# LEDs.net
KiCad netlist of a schematic drawn in Altium Designer
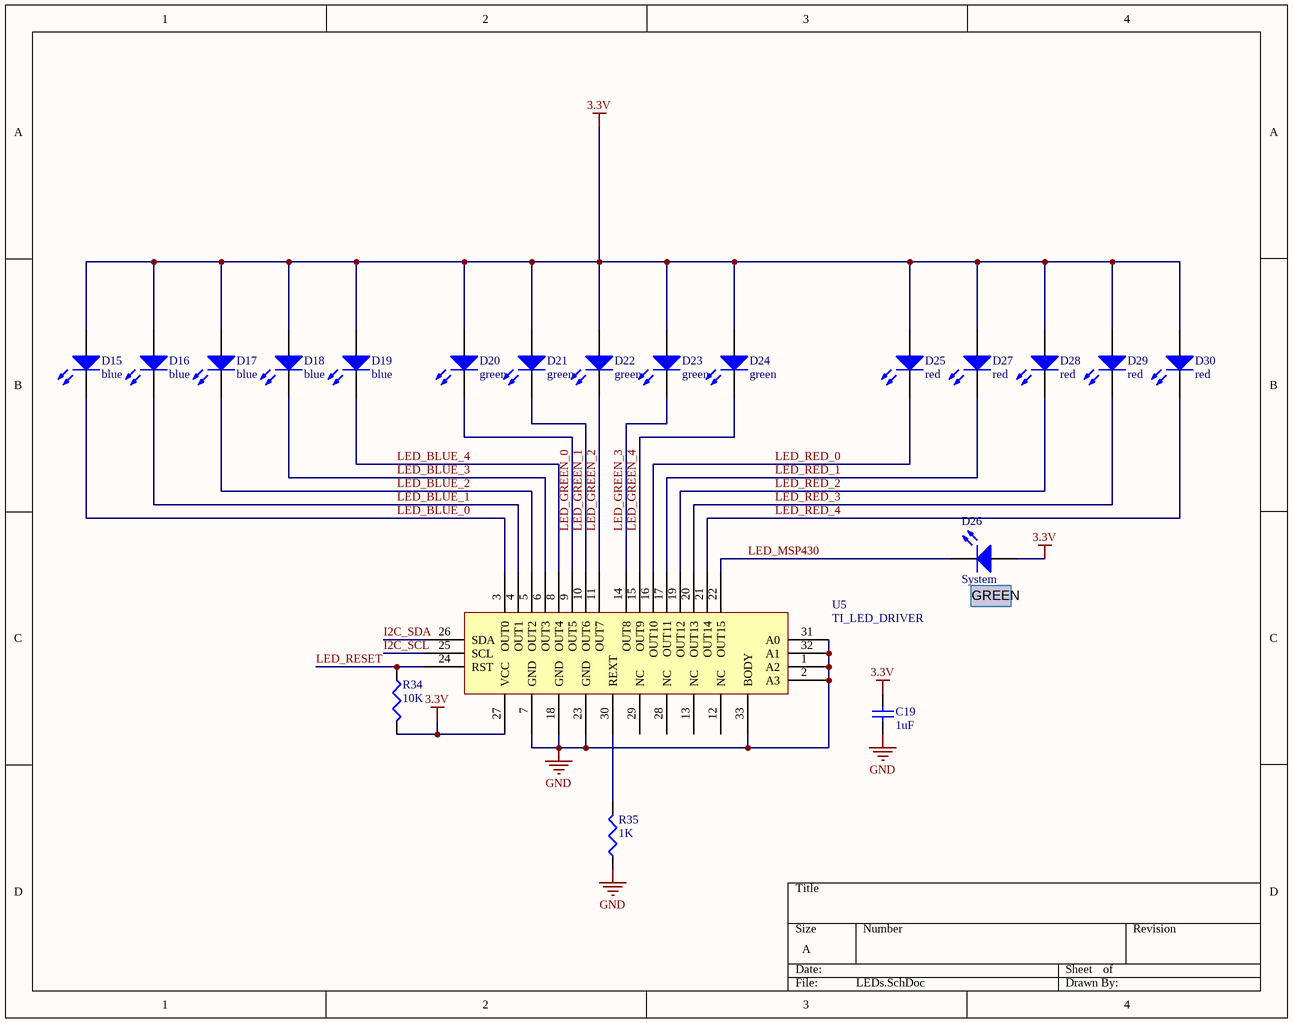
[diagram p0: LEDs.SchDoc]

(export (version "E")
  (design (tool "Eeschema 10.0.6"))
  (components
    (comp (ref "C19")
      (value "1uF")
      (footprint "CAPC1608L")
      (description "Capacitor (Semiconductor SIM Model)")
      (fields (field (name "Comment") "Cap Semi") (field (name "PUBLISHER") "Altium Limited"))
      (libsource (lib "Miscellaneous Devices") (part "Cap Semi"))
    )
    (comp (ref "D15") (value "blue") (footprint "SurfaceMount(603)") (libsource (lib "") (part "LED_1")))
    (comp (ref "D16") (value "blue") (footprint "SurfaceMount(603)") (libsource (lib "") (part "LED_1")))
    (comp (ref "D17") (value "blue") (footprint "SurfaceMount(603)") (libsource (lib "") (part "LED_1")))
    (comp (ref "D18") (value "blue") (footprint "SurfaceMount(603)") (libsource (lib "") (part "LED_1")))
    (comp (ref "D19") (value "blue") (footprint "SurfaceMount(603)") (libsource (lib "") (part "LED_1")))
    (comp (ref "D20") (value "green") (footprint "SurfaceMount(603)") (libsource (lib "") (part "LED_1")))
    (comp (ref "D21") (value "green") (footprint "SurfaceMount(603)") (libsource (lib "") (part "LED_1")))
    (comp (ref "D22") (value "green") (footprint "SurfaceMount(603)") (libsource (lib "") (part "LED_1")))
    (comp (ref "D23") (value "green") (footprint "SurfaceMount(603)") (libsource (lib "") (part "LED_1")))
    (comp (ref "D24") (value "green") (footprint "SurfaceMount(603)") (libsource (lib "") (part "LED_1")))
    (comp (ref "D25") (value "red") (footprint "SurfaceMount(603)") (libsource (lib "") (part "LED_1")))
    (comp (ref "D26") (value "System") (footprint "SurfaceMount(603)") (libsource (lib "mrone") (part "LED")))
    (comp (ref "D27") (value "red") (footprint "SurfaceMount(603)") (libsource (lib "") (part "LED_1")))
    (comp (ref "D28") (value "red") (footprint "SurfaceMount(603)") (libsource (lib "") (part "LED_1")))
    (comp (ref "D29") (value "red") (footprint "SurfaceMount(603)") (libsource (lib "") (part "LED_1")))
    (comp (ref "D30") (value "red") (footprint "SurfaceMount(603)") (libsource (lib "") (part "LED_1")))
    (comp (ref "R34")
      (value "10K")
      (footprint "RESC1608L")
      (description "Resistor")
      (fields (field (name "Comment") "Res3") (field (name "PUBLISHER") "Altium Limited"))
      (libsource (lib "Miscellaneous Devices") (part "Res3"))
    )
    (comp (ref "R35")
      (value "1K")
      (footprint "RESC1608L")
      (description "Resistor")
      (fields (field (name "Comment") "Res3") (field (name "PUBLISHER") "Altium Limited"))
      (libsource (lib "Miscellaneous Devices") (part "Res3"))
    )
    (comp (ref "U5")
      (value "TI_LED_DRIVER")
      (footprint "QFN32-LEDTLC59116")
      (libsource (lib "mrone") (part "TLC59116LEDDRIVER"))
    )
  )
  (nets
    (net (code "1") (name "/I2C_SCL") (class "Default")
      (node (ref "U5") (pin "25") (pinfunction "SCL_25") (pintype "passive"))
    )
    (net (code "2") (name "/I2C_SDA") (class "Default")
      (node (ref "U5") (pin "26") (pinfunction "SDA_26") (pintype "passive"))
    )
    (net (code "3") (name "/LED_BLUE_0") (class "Default")
      (node (ref "D15") (pin "2") (pinfunction "K_2") (pintype "passive"))
      (node (ref "U5") (pin "3") (pinfunction "OUT0_3") (pintype "passive"))
    )
    (net (code "4") (name "/LED_BLUE_1") (class "Default")
      (node (ref "D16") (pin "2") (pinfunction "K_2") (pintype "passive"))
      (node (ref "U5") (pin "4") (pinfunction "OUT1_4") (pintype "passive"))
    )
    (net (code "5") (name "/LED_BLUE_2") (class "Default")
      (node (ref "D17") (pin "2") (pinfunction "K_2") (pintype "passive"))
      (node (ref "U5") (pin "5") (pinfunction "OUT2_5") (pintype "passive"))
    )
    (net (code "6") (name "/LED_BLUE_3") (class "Default")
      (node (ref "D18") (pin "2") (pinfunction "K_2") (pintype "passive"))
      (node (ref "U5") (pin "6") (pinfunction "OUT3_6") (pintype "passive"))
    )
    (net (code "7") (name "/LED_BLUE_4") (class "Default")
      (node (ref "D19") (pin "2") (pinfunction "K_2") (pintype "passive"))
      (node (ref "U5") (pin "8") (pinfunction "OUT4_8") (pintype "passive"))
    )
    (net (code "8") (name "/LED_GREEN_0") (class "Default")
      (node (ref "D20") (pin "2") (pinfunction "K_2") (pintype "passive"))
      (node (ref "U5") (pin "9") (pinfunction "OUT5_9") (pintype "passive"))
    )
    (net (code "9") (name "/LED_GREEN_1") (class "Default")
      (node (ref "D21") (pin "2") (pinfunction "K_2") (pintype "passive"))
      (node (ref "U5") (pin "10") (pinfunction "OUT6_10") (pintype "passive"))
    )
    (net (code "10") (name "/LED_GREEN_2") (class "Default")
      (node (ref "D22") (pin "2") (pinfunction "K_2") (pintype "passive"))
      (node (ref "U5") (pin "11") (pinfunction "OUT7_11") (pintype "passive"))
    )
    (net (code "11") (name "/LED_GREEN_3") (class "Default")
      (node (ref "D23") (pin "2") (pinfunction "K_2") (pintype "passive"))
      (node (ref "U5") (pin "14") (pinfunction "OUT8_14") (pintype "passive"))
    )
    (net (code "12") (name "/LED_GREEN_4") (class "Default")
      (node (ref "D24") (pin "2") (pinfunction "K_2") (pintype "passive"))
      (node (ref "U5") (pin "15") (pinfunction "OUT9_15") (pintype "passive"))
    )
    (net (code "13") (name "/LED_MSP430") (class "Default")
      (node (ref "D26") (pin "2") (pinfunction "K_2") (pintype "passive"))
      (node (ref "U5") (pin "22") (pinfunction "OUT15_22") (pintype "passive"))
    )
    (net (code "14") (name "/LED_RED_0") (class "Default")
      (node (ref "D25") (pin "2") (pinfunction "K_2") (pintype "passive"))
      (node (ref "U5") (pin "16") (pinfunction "OUT10_16") (pintype "passive"))
    )
    (net (code "15") (name "/LED_RED_1") (class "Default")
      (node (ref "D27") (pin "2") (pinfunction "K_2") (pintype "passive"))
      (node (ref "U5") (pin "17") (pinfunction "OUT11_17") (pintype "passive"))
    )
    (net (code "16") (name "/LED_RED_2") (class "Default")
      (node (ref "D28") (pin "2") (pinfunction "K_2") (pintype "passive"))
      (node (ref "U5") (pin "19") (pinfunction "OUT12_19") (pintype "passive"))
    )
    (net (code "17") (name "/LED_RED_3") (class "Default")
      (node (ref "D29") (pin "2") (pinfunction "K_2") (pintype "passive"))
      (node (ref "U5") (pin "20") (pinfunction "OUT13_20") (pintype "passive"))
    )
    (net (code "18") (name "/LED_RED_4") (class "Default")
      (node (ref "D30") (pin "2") (pinfunction "K_2") (pintype "passive"))
      (node (ref "U5") (pin "21") (pinfunction "OUT14_21") (pintype "passive"))
    )
    (net (code "19") (name "/LED_RESET") (class "Default")
      (node (ref "R34") (pin "1") (pinfunction "1_1") (pintype "passive"))
      (node (ref "U5") (pin "24") (pinfunction "RST_24") (pintype "passive"))
    )
    (net (code "20") (name "3.3V") (class "Default")
      (node (ref "C19") (pin "2") (pinfunction "2_2") (pintype "passive"))
      (node (ref "D15") (pin "1") (pinfunction "A_1") (pintype "passive"))
      (node (ref "D16") (pin "1") (pinfunction "A_1") (pintype "passive"))
      (node (ref "D17") (pin "1") (pinfunction "A_1") (pintype "passive"))
      (node (ref "D18") (pin "1") (pinfunction "A_1") (pintype "passive"))
      (node (ref "D19") (pin "1") (pinfunction "A_1") (pintype "passive"))
      (node (ref "D20") (pin "1") (pinfunction "A_1") (pintype "passive"))
      (node (ref "D21") (pin "1") (pinfunction "A_1") (pintype "passive"))
      (node (ref "D22") (pin "1") (pinfunction "A_1") (pintype "passive"))
      (node (ref "D23") (pin "1") (pinfunction "A_1") (pintype "passive"))
      (node (ref "D24") (pin "1") (pinfunction "A_1") (pintype "passive"))
      (node (ref "D25") (pin "1") (pinfunction "A_1") (pintype "passive"))
      (node (ref "D26") (pin "1") (pinfunction "A_1") (pintype "passive"))
      (node (ref "D27") (pin "1") (pinfunction "A_1") (pintype "passive"))
      (node (ref "D28") (pin "1") (pinfunction "A_1") (pintype "passive"))
      (node (ref "D29") (pin "1") (pinfunction "A_1") (pintype "passive"))
      (node (ref "D30") (pin "1") (pinfunction "A_1") (pintype "passive"))
      (node (ref "R34") (pin "2") (pinfunction "2_2") (pintype "passive"))
      (node (ref "U5") (pin "27") (pinfunction "VCC_27") (pintype "passive"))
    )
    (net (code "21") (name "GND") (class "Default")
      (node (ref "C19") (pin "1") (pinfunction "1_1") (pintype "passive"))
      (node (ref "R35") (pin "1") (pinfunction "1_1") (pintype "passive"))
      (node (ref "U5") (pin "1") (pinfunction "A2_1") (pintype "passive"))
      (node (ref "U5") (pin "18") (pinfunction "GND_18") (pintype "passive"))
      (node (ref "U5") (pin "2") (pinfunction "A3_2") (pintype "passive"))
      (node (ref "U5") (pin "23") (pinfunction "GND_23") (pintype "passive"))
      (node (ref "U5") (pin "31") (pinfunction "A0_31") (pintype "passive"))
      (node (ref "U5") (pin "32") (pinfunction "A1_32") (pintype "passive"))
      (node (ref "U5") (pin "33") (pinfunction "BODY_33") (pintype "passive"))
      (node (ref "U5") (pin "7") (pinfunction "GND_7") (pintype "passive"))
    )
    (net (code "22") (name "Net-(U5-REXT)") (class "Default")
      (node (ref "R35") (pin "2") (pinfunction "2_2") (pintype "passive"))
      (node (ref "U5") (pin "30") (pinfunction "REXT_30") (pintype "passive"))
    )
    (net (code "23") (name "unconnected-(U5-NC-Pad12)") (class "Default")
      (node (ref "U5") (pin "12") (pinfunction "NC_12") (pintype "passive"))
    )
    (net (code "24") (name "unconnected-(U5-NC-Pad13)") (class "Default")
      (node (ref "U5") (pin "13") (pinfunction "NC_13") (pintype "passive"))
    )
    (net (code "25") (name "unconnected-(U5-NC-Pad28)") (class "Default")
      (node (ref "U5") (pin "28") (pinfunction "NC_28") (pintype "passive"))
    )
    (net (code "26") (name "unconnected-(U5-NC-Pad29)") (class "Default")
      (node (ref "U5") (pin "29") (pinfunction "NC_29") (pintype "passive"))
    )
  )
)
